# config-serdes.net
KiCad netlist of a schematic drawn in Altium Designer
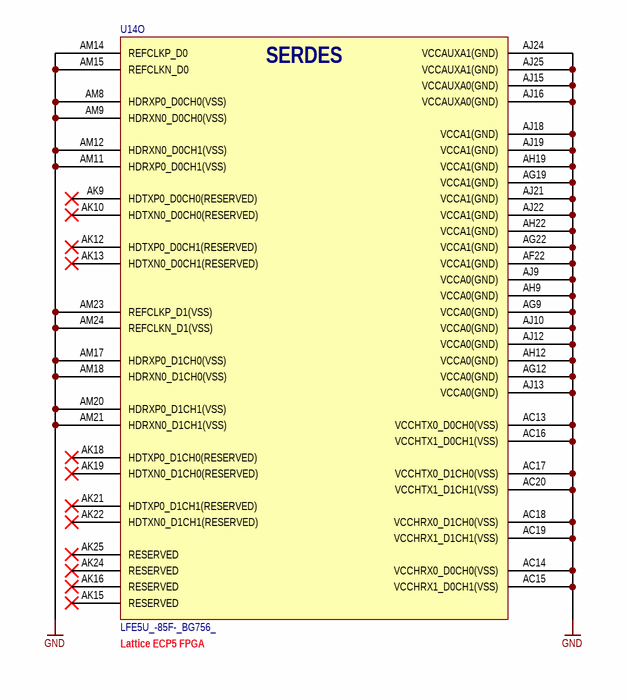
[diagram p0: config-serdes.SchDoc]

(export (version "E")
  (design (tool "Eeschema 10.0.6"))
  (components
    (comp (ref "U14")
      (value "LFE5U_-85F-_BG756_")
      (footprint "lattice:caBGA756")
      (description "ECP5 FPGA, 85k LUT, 756-caBGA")
      (fields (field (name "MANUFACTURER") "Lattice Semiconductor"))
      (libsource (lib "lattice") (part "LFE5U_-85F-_BG756_"))
    )
  )
  (nets
    (net (code "1") (name "GND") (class "Default")
      (node (ref "U14") (pin "AC13") (pinfunction "VCCHTX0_D0CH0(VSS)_AC13") (pintype "power_in"))
      (node (ref "U14") (pin "AC14") (pinfunction "VCCHRX0_D0CH0(VSS)_AC14") (pintype "power_in"))
      (node (ref "U14") (pin "AC15") (pinfunction "VCCHRX1_D0CH1(VSS)_AC15") (pintype "power_in"))
      (node (ref "U14") (pin "AC16") (pinfunction "VCCHTX1_D0CH1(VSS)_AC16") (pintype "power_in"))
      (node (ref "U14") (pin "AC17") (pinfunction "VCCHTX0_D1CH0(VSS)_AC17") (pintype "power_in"))
      (node (ref "U14") (pin "AC18") (pinfunction "VCCHRX0_D1CH0(VSS)_AC18") (pintype "power_in"))
      (node (ref "U14") (pin "AC19") (pinfunction "VCCHRX1_D1CH1(VSS)_AC19") (pintype "power_in"))
      (node (ref "U14") (pin "AC20") (pinfunction "VCCHTX1_D1CH1(VSS)_AC20") (pintype "power_in"))
      (node (ref "U14") (pin "AF22") (pinfunction "VCCA1(GND)_AF22") (pintype "power_in"))
      (node (ref "U14") (pin "AG12") (pinfunction "VCCA0(GND)_AG12") (pintype "power_in"))
      (node (ref "U14") (pin "AG19") (pinfunction "VCCA1(GND)_AG19") (pintype "power_in"))
      (node (ref "U14") (pin "AG22") (pinfunction "VCCA1(GND)_AG22") (pintype "power_in"))
      (node (ref "U14") (pin "AG9") (pinfunction "VCCA0(GND)_AG9") (pintype "power_in"))
      (node (ref "U14") (pin "AH12") (pinfunction "VCCA0(GND)_AH12") (pintype "power_in"))
      (node (ref "U14") (pin "AH19") (pinfunction "VCCA1(GND)_AH19") (pintype "power_in"))
      (node (ref "U14") (pin "AH22") (pinfunction "VCCA1(GND)_AH22") (pintype "power_in"))
      (node (ref "U14") (pin "AH9") (pinfunction "VCCA0(GND)_AH9") (pintype "power_in"))
      (node (ref "U14") (pin "AJ10") (pinfunction "VCCA0(GND)_AJ10") (pintype "power_in"))
      (node (ref "U14") (pin "AJ12") (pinfunction "VCCA0(GND)_AJ12") (pintype "power_in"))
      (node (ref "U14") (pin "AJ13") (pinfunction "VCCA0(GND)_AJ13") (pintype "power_in"))
      (node (ref "U14") (pin "AJ15") (pinfunction "VCCAUXA0(GND)_AJ15") (pintype "power_in"))
      (node (ref "U14") (pin "AJ16") (pinfunction "VCCAUXA0(GND)_AJ16") (pintype "power_in"))
      (node (ref "U14") (pin "AJ18") (pinfunction "VCCA1(GND)_AJ18") (pintype "power_in"))
      (node (ref "U14") (pin "AJ19") (pinfunction "VCCA1(GND)_AJ19") (pintype "power_in"))
      (node (ref "U14") (pin "AJ21") (pinfunction "VCCA1(GND)_AJ21") (pintype "power_in"))
      (node (ref "U14") (pin "AJ22") (pinfunction "VCCA1(GND)_AJ22") (pintype "power_in"))
      (node (ref "U14") (pin "AJ24") (pinfunction "VCCAUXA1(GND)_AJ24") (pintype "power_in"))
      (node (ref "U14") (pin "AJ25") (pinfunction "VCCAUXA1(GND)_AJ25") (pintype "power_in"))
      (node (ref "U14") (pin "AJ9") (pinfunction "VCCA0(GND)_AJ9") (pintype "power_in"))
      (node (ref "U14") (pin "AM11") (pinfunction "HDRXP0_D0CH1(VSS)_AM11") (pintype "passive"))
      (node (ref "U14") (pin "AM12") (pinfunction "HDRXN0_D0CH1(VSS)_AM12") (pintype "passive"))
      (node (ref "U14") (pin "AM14") (pinfunction "REFCLKP_D0_AM14") (pintype "passive"))
      (node (ref "U14") (pin "AM15") (pinfunction "REFCLKN_D0_AM15") (pintype "passive"))
      (node (ref "U14") (pin "AM17") (pinfunction "HDRXP0_D1CH0(VSS)_AM17") (pintype "passive"))
      (node (ref "U14") (pin "AM18") (pinfunction "HDRXN0_D1CH0(VSS)_AM18") (pintype "passive"))
      (node (ref "U14") (pin "AM20") (pinfunction "HDRXP0_D1CH1(VSS)_AM20") (pintype "passive"))
      (node (ref "U14") (pin "AM21") (pinfunction "HDRXN0_D1CH1(VSS)_AM21") (pintype "passive"))
      (node (ref "U14") (pin "AM23") (pinfunction "REFCLKP_D1(VSS)_AM23") (pintype "passive"))
      (node (ref "U14") (pin "AM24") (pinfunction "REFCLKN_D1(VSS)_AM24") (pintype "passive"))
      (node (ref "U14") (pin "AM8") (pinfunction "HDRXP0_D0CH0(VSS)_AM8") (pintype "passive"))
      (node (ref "U14") (pin "AM9") (pinfunction "HDRXN0_D0CH0(VSS)_AM9") (pintype "passive"))
    )
    (net (code "2") (name "unconnected-(U14O-HDTXN0_D0CH0(RESERVED)-PadAK10)") (class "Default")
      (node (ref "U14") (pin "AK10") (pinfunction "HDTXN0_D0CH0(RESERVED)_AK10") (pintype "passive+no_connect"))
    )
    (net (code "3") (name "unconnected-(U14O-HDTXN0_D0CH1(RESERVED)-PadAK13)") (class "Default")
      (node (ref "U14") (pin "AK13") (pinfunction "HDTXN0_D0CH1(RESERVED)_AK13") (pintype "passive+no_connect"))
    )
    (net (code "4") (name "unconnected-(U14O-HDTXN0_D1CH0(RESERVED)-PadAK19)") (class "Default")
      (node (ref "U14") (pin "AK19") (pinfunction "HDTXN0_D1CH0(RESERVED)_AK19") (pintype "passive+no_connect"))
    )
    (net (code "5") (name "unconnected-(U14O-HDTXN0_D1CH1(RESERVED)-PadAK22)") (class "Default")
      (node (ref "U14") (pin "AK22") (pinfunction "HDTXN0_D1CH1(RESERVED)_AK22") (pintype "passive+no_connect"))
    )
    (net (code "6") (name "unconnected-(U14O-HDTXP0_D0CH0(RESERVED)-PadAK9)") (class "Default")
      (node (ref "U14") (pin "AK9") (pinfunction "HDTXP0_D0CH0(RESERVED)_AK9") (pintype "passive+no_connect"))
    )
    (net (code "7") (name "unconnected-(U14O-HDTXP0_D0CH1(RESERVED)-PadAK12)") (class "Default")
      (node (ref "U14") (pin "AK12") (pinfunction "HDTXP0_D0CH1(RESERVED)_AK12") (pintype "passive+no_connect"))
    )
    (net (code "8") (name "unconnected-(U14O-HDTXP0_D1CH0(RESERVED)-PadAK18)") (class "Default")
      (node (ref "U14") (pin "AK18") (pinfunction "HDTXP0_D1CH0(RESERVED)_AK18") (pintype "passive+no_connect"))
    )
    (net (code "9") (name "unconnected-(U14O-HDTXP0_D1CH1(RESERVED)-PadAK21)") (class "Default")
      (node (ref "U14") (pin "AK21") (pinfunction "HDTXP0_D1CH1(RESERVED)_AK21") (pintype "passive+no_connect"))
    )
    (net (code "10") (name "unconnected-(U14O-RESERVED-PadAK15)") (class "Default")
      (node (ref "U14") (pin "AK15") (pinfunction "RESERVED_AK15") (pintype "passive+no_connect"))
    )
    (net (code "11") (name "unconnected-(U14O-RESERVED-PadAK16)") (class "Default")
      (node (ref "U14") (pin "AK16") (pinfunction "RESERVED_AK16") (pintype "passive+no_connect"))
    )
    (net (code "12") (name "unconnected-(U14O-RESERVED-PadAK24)") (class "Default")
      (node (ref "U14") (pin "AK24") (pinfunction "RESERVED_AK24") (pintype "passive+no_connect"))
    )
    (net (code "13") (name "unconnected-(U14O-RESERVED-PadAK25)") (class "Default")
      (node (ref "U14") (pin "AK25") (pinfunction "RESERVED_AK25") (pintype "passive+no_connect"))
    )
  )
)
